# mcu_v06.net
KiCad netlist of a schematic drawn in EAGLE
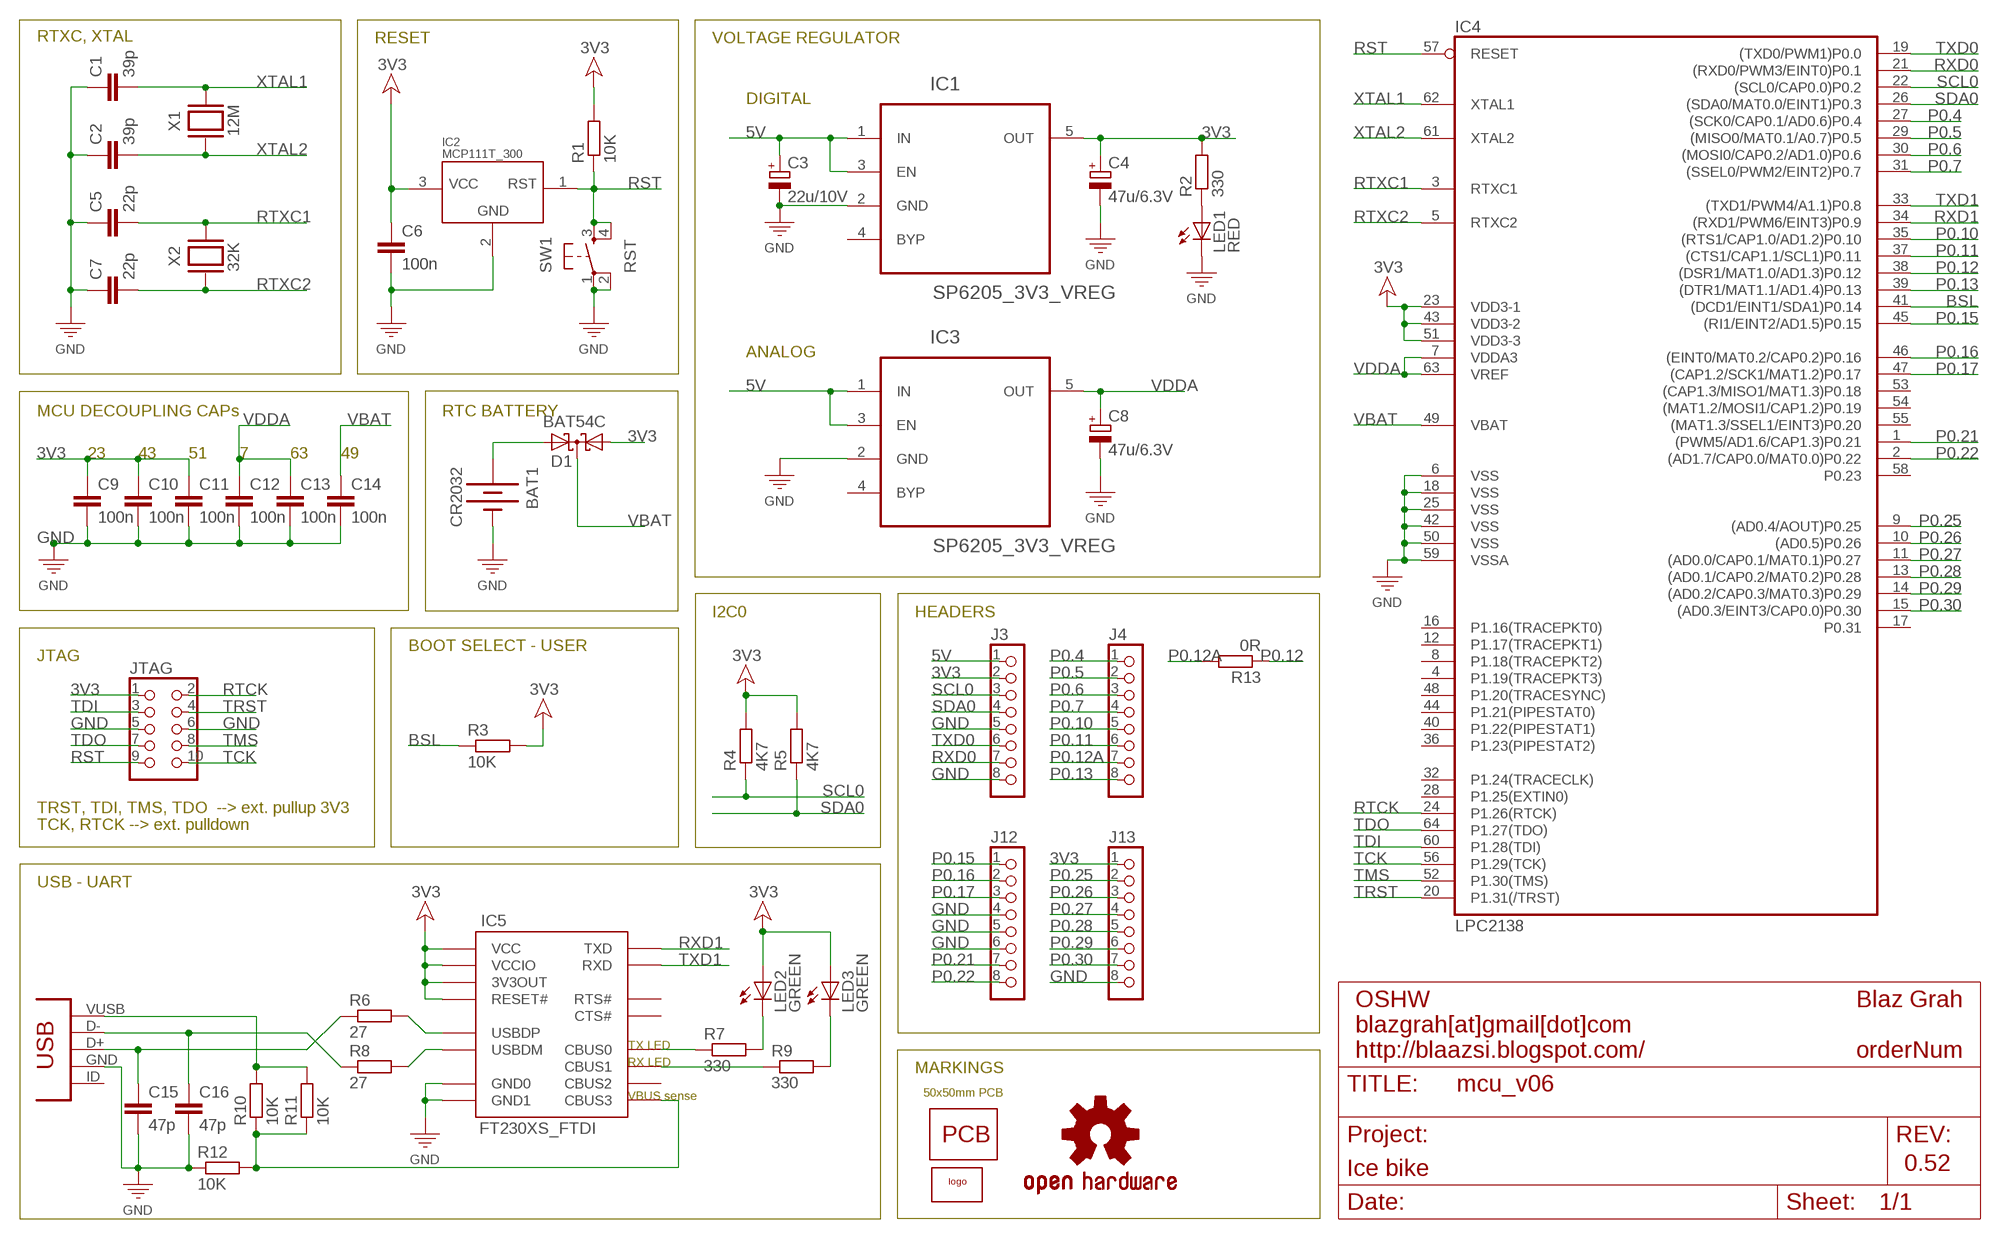
[diagram p0: schematic, sheet 1]

(export (version "E")
  (design (tool "Eeschema 10.0.6"))
  (components
    (comp (ref "BAT1")
      (value "CR2032")
      (footprint "eagle-import:BATTERY_20MM_SMD")
      (libsource (lib "eagle-import") (part "BATTERY20MM"))
    )
    (comp (ref "C1")
      (value "39p")
      (footprint "eagle-import:C0603")
      (libsource (lib "eagle-import") (part "C-EUC0603"))
    )
    (comp (ref "C2")
      (value "39p")
      (footprint "eagle-import:C0603")
      (libsource (lib "eagle-import") (part "C-EUC0603"))
    )
    (comp (ref "C3")
      (value "22u/10V")
      (footprint "eagle-import:SMC_B")
      (libsource (lib "eagle-import") (part "CAPACITOR_POL-SMC_B"))
    )
    (comp (ref "C4")
      (value "47u/6.3V")
      (footprint "eagle-import:SMC_B")
      (libsource (lib "eagle-import") (part "CAPACITOR_POL-SMC_B"))
    )
    (comp (ref "C5")
      (value "22p")
      (footprint "eagle-import:C0603")
      (libsource (lib "eagle-import") (part "C-EUC0603"))
    )
    (comp (ref "C6")
      (value "100n")
      (footprint "eagle-import:C0603")
      (libsource (lib "eagle-import") (part "C-EUC0603"))
    )
    (comp (ref "C7")
      (value "22p")
      (footprint "eagle-import:C0603")
      (libsource (lib "eagle-import") (part "C-EUC0603"))
    )
    (comp (ref "C8")
      (value "47u/6.3V")
      (footprint "eagle-import:SMC_B")
      (libsource (lib "eagle-import") (part "CAPACITOR_POL-SMC_B"))
    )
    (comp (ref "C9")
      (value "100n")
      (footprint "eagle-import:C0603")
      (libsource (lib "eagle-import") (part "C-EUC0603"))
    )
    (comp (ref "C10")
      (value "100n")
      (footprint "eagle-import:C0603")
      (libsource (lib "eagle-import") (part "C-EUC0603"))
    )
    (comp (ref "C11")
      (value "100n")
      (footprint "eagle-import:C0603")
      (libsource (lib "eagle-import") (part "C-EUC0603"))
    )
    (comp (ref "C12")
      (value "100n")
      (footprint "eagle-import:C0603")
      (libsource (lib "eagle-import") (part "C-EUC0603"))
    )
    (comp (ref "C13")
      (value "100n")
      (footprint "eagle-import:C0603")
      (libsource (lib "eagle-import") (part "C-EUC0603"))
    )
    (comp (ref "C14")
      (value "100n")
      (footprint "eagle-import:C0603")
      (libsource (lib "eagle-import") (part "C-EUC0603"))
    )
    (comp (ref "C15")
      (value "47p")
      (footprint "eagle-import:C0603")
      (libsource (lib "eagle-import") (part "C-EUC0603"))
    )
    (comp (ref "C16")
      (value "47p")
      (footprint "eagle-import:C0603")
      (libsource (lib "eagle-import") (part "C-EUC0603"))
    )
    (comp (ref "D1")
      (value "BAT54C")
      (footprint "eagle-import:SOT23")
      (libsource (lib "eagle-import") (part "BAT54C"))
    )
    (comp (ref "DOC")
      (value "FRAME_DINA4_L")
      (footprint "eagle-import:DP_LOGO")
      (fields
        (field (name "AUTHOR") "Blaz Grah")
        (field (name "DATE") "23.4.2012")
        (field (name "LICENSE") "OSHW")
        (field (name "PROJECT") "Ice bike")
        (field (name "REV") "0.52")
        (field (name "URL1") "blazgrah[at]gmail[dot]com")
        (field (name "URL2") "http://blaazsi.blogspot.com/")
      )
      (libsource (lib "eagle-import") (part "FRAME_DINA4_L"))
    )
    (comp (ref "IC1")
      (value "SP6205_3V3_VREG")
      (footprint "eagle-import:SOT23-5")
      (libsource (lib "eagle-import") (part "SP6205_3V3_VREG"))
    )
    (comp (ref "IC2")
      (value "MCP111T_300")
      (footprint "eagle-import:SOT23")
      (libsource (lib "eagle-import") (part "MCP111T_300"))
    )
    (comp (ref "IC3")
      (value "SP6205_3V3_VREG")
      (footprint "eagle-import:SOT23-5")
      (libsource (lib "eagle-import") (part "SP6205_3V3_VREG"))
    )
    (comp (ref "IC4")
      (value "LPC2138")
      (footprint "eagle-import:LQFP64")
      (libsource (lib "eagle-import") (part "LCP2138_LQFP64"))
    )
    (comp (ref "IC5")
      (value "FT230XS_FTDI")
      (footprint "eagle-import:SSOP16")
      (libsource (lib "eagle-import") (part "FT230XS_FTDI"))
    )
    (comp (ref "J3")
      (value "CON_HEADER_1X08-PTH")
      (footprint "eagle-import:M1X8")
      (libsource (lib "eagle-import") (part "CON_HEADER_1X08-PTH"))
    )
    (comp (ref "J4")
      (value "CON_HEADER_1X08-PTH")
      (footprint "eagle-import:M1X8")
      (libsource (lib "eagle-import") (part "CON_HEADER_1X08-PTH"))
    )
    (comp (ref "J12")
      (value "CON_HEADER_1X08-PTH")
      (footprint "eagle-import:M1X8")
      (libsource (lib "eagle-import") (part "CON_HEADER_1X08-PTH"))
    )
    (comp (ref "J13")
      (value "CON_HEADER_1X08-PTH")
      (footprint "eagle-import:M1X8")
      (libsource (lib "eagle-import") (part "CON_HEADER_1X08-PTH"))
    )
    (comp (ref "JTAG")
      (value "CON_HEADER_2X05-PTH+SHROUDED_A")
      (footprint "eagle-import:PINSHRD_PTH_2X05")
      (libsource (lib "eagle-import") (part "CON_HEADER_2X05-PTH+SHROUDED_A"))
    )
    (comp (ref "LED1")
      (value "RED")
      (footprint "eagle-import:LED0805")
      (libsource (lib "eagle-import") (part "LED0805"))
    )
    (comp (ref "LED2")
      (value "GREEN")
      (footprint "eagle-import:LED0805")
      (libsource (lib "eagle-import") (part "LED0805"))
    )
    (comp (ref "LED3")
      (value "GREEN")
      (footprint "eagle-import:LED0805")
      (libsource (lib "eagle-import") (part "LED0805"))
    )
    (comp (ref "LOGO1")
      (value "OSHW-LOGOS")
      (footprint "eagle-import:OSHW-LOGO-S")
      (libsource (lib "eagle-import") (part "OSHW-LOGOS"))
    )
    (comp (ref "PCB1")
      (value "PCB")
      (footprint "eagle-import:PCB_50X50")
      (libsource (lib "eagle-import") (part "PCB"))
    )
    (comp (ref "R1")
      (value "10K")
      (footprint "eagle-import:R0603")
      (libsource (lib "eagle-import") (part "R-EU0603"))
    )
    (comp (ref "R2")
      (value "330")
      (footprint "eagle-import:R0603")
      (libsource (lib "eagle-import") (part "R-EU0603"))
    )
    (comp (ref "R3")
      (value "10K")
      (footprint "eagle-import:R0603")
      (libsource (lib "eagle-import") (part "R-EU0603"))
    )
    (comp (ref "R4")
      (value "4K7")
      (footprint "eagle-import:R0603")
      (libsource (lib "eagle-import") (part "R-EU0603"))
    )
    (comp (ref "R5")
      (value "4K7")
      (footprint "eagle-import:R0603")
      (libsource (lib "eagle-import") (part "R-EU0603"))
    )
    (comp (ref "R6")
      (value "27")
      (footprint "eagle-import:R0603")
      (libsource (lib "eagle-import") (part "R-EU0603"))
    )
    (comp (ref "R7")
      (value "330")
      (footprint "eagle-import:R0603")
      (libsource (lib "eagle-import") (part "R-EU0603"))
    )
    (comp (ref "R8")
      (value "27")
      (footprint "eagle-import:R0603")
      (libsource (lib "eagle-import") (part "R-EU0603"))
    )
    (comp (ref "R9")
      (value "330")
      (footprint "eagle-import:R0603")
      (libsource (lib "eagle-import") (part "R-EU0603"))
    )
    (comp (ref "R10")
      (value "10K")
      (footprint "eagle-import:R0603")
      (libsource (lib "eagle-import") (part "R-EU0603"))
    )
    (comp (ref "R11")
      (value "10K")
      (footprint "eagle-import:R0603")
      (libsource (lib "eagle-import") (part "R-EU0603"))
    )
    (comp (ref "R12")
      (value "10K")
      (footprint "eagle-import:R0603")
      (libsource (lib "eagle-import") (part "R-EU0603"))
    )
    (comp (ref "R13")
      (value "0R")
      (footprint "eagle-import:R0603_JUMP")
      (libsource (lib "eagle-import") (part "R-EU0603J"))
    )
    (comp (ref "SW1")
      (value "RST")
      (footprint "eagle-import:BUTTON_SW_4P_SMD")
      (libsource (lib "eagle-import") (part "TACTIL_BUTTON"))
    )
    (comp (ref "U$13")
      (value "LOGO")
      (footprint "eagle-import:LOGO_SMILE")
      (libsource (lib "eagle-import") (part "LOGO"))
    )
    (comp (ref "USB1")
      (value "CON-USB-F-MINI-B")
      (footprint "eagle-import:CONN_USB_MINI-B")
      (libsource (lib "eagle-import") (part "CON-USB-F-MINI-B"))
    )
    (comp (ref "X1")
      (value "12M")
      (footprint "eagle-import:CRYSTAL_12M_4.8X10.6MM")
      (libsource (lib "eagle-import") (part "CRYSTALSMD_4.8X10.6"))
    )
    (comp (ref "X2")
      (value "32K")
      (footprint "eagle-import:CRYSTAL_32K_SMD")
      (libsource (lib "eagle-import") (part "CRYSTALSMD_32K"))
    )
  )
  (nets
    (net (code "1") (name "/5V") (class "Default")
      (node (ref "C3") (pin "+") (pinfunction "+_+") (pintype "passive"))
      (node (ref "IC1") (pin "1") (pinfunction "IN_1") (pintype "input"))
      (node (ref "IC1") (pin "3") (pinfunction "EN_3") (pintype "input"))
      (node (ref "IC3") (pin "1") (pinfunction "IN_1") (pintype "input"))
      (node (ref "IC3") (pin "3") (pinfunction "EN_3") (pintype "input"))
      (node (ref "J3") (pin "1") (pinfunction "1_1") (pintype "passive"))
    )
    (net (code "2") (name "/BSL") (class "Default")
      (node (ref "IC4") (pin "41") (pinfunction "(DCD1/EINT1/SDA1)P0.14_41") (pintype "bidirectional"))
      (node (ref "R3") (pin "1") (pinfunction "1_1") (pintype "passive"))
    )
    (net (code "3") (name "/P0.4") (class "Default")
      (node (ref "IC4") (pin "27") (pinfunction "(SCK0/CAP0.1/AD0.6)P0.4_27") (pintype "bidirectional"))
      (node (ref "J4") (pin "1") (pinfunction "1_1") (pintype "passive"))
    )
    (net (code "4") (name "/P0.5") (class "Default")
      (node (ref "IC4") (pin "29") (pinfunction "(MISO0/MAT0.1/A0.7)P0.5_29") (pintype "bidirectional"))
      (node (ref "J4") (pin "2") (pinfunction "2_2") (pintype "passive"))
    )
    (net (code "5") (name "/P0.6") (class "Default")
      (node (ref "IC4") (pin "30") (pinfunction "(MOSI0/CAP0.2/AD1.0)P0.6_30") (pintype "bidirectional"))
      (node (ref "J4") (pin "3") (pinfunction "3_3") (pintype "passive"))
    )
    (net (code "6") (name "/P0.7") (class "Default")
      (node (ref "IC4") (pin "31") (pinfunction "(SSEL0/PWM2/EINT2)P0.7_31") (pintype "bidirectional"))
      (node (ref "J4") (pin "4") (pinfunction "4_4") (pintype "passive"))
    )
    (net (code "7") (name "/P0.10") (class "Default")
      (node (ref "IC4") (pin "35") (pinfunction "(RTS1/CAP1.0/AD1.2)P0.10_35") (pintype "bidirectional"))
      (node (ref "J4") (pin "5") (pinfunction "5_5") (pintype "passive"))
    )
    (net (code "8") (name "/P0.11") (class "Default")
      (node (ref "IC4") (pin "37") (pinfunction "(CTS1/CAP1.1/SCL1)P0.11_37") (pintype "bidirectional"))
      (node (ref "J4") (pin "6") (pinfunction "6_6") (pintype "passive"))
    )
    (net (code "9") (name "/P0.12") (class "Default")
      (node (ref "IC4") (pin "38") (pinfunction "(DSR1/MAT1.0/AD1.3)P0.12_38") (pintype "bidirectional"))
      (node (ref "R13") (pin "1") (pinfunction "1_1") (pintype "passive"))
    )
    (net (code "10") (name "/P0.12A") (class "Default")
      (node (ref "J4") (pin "7") (pinfunction "7_7") (pintype "passive"))
      (node (ref "R13") (pin "2") (pinfunction "2_2") (pintype "passive"))
    )
    (net (code "11") (name "/P0.13") (class "Default")
      (node (ref "IC4") (pin "39") (pinfunction "(DTR1/MAT1.1/AD1.4)P0.13_39") (pintype "bidirectional"))
      (node (ref "J4") (pin "8") (pinfunction "8_8") (pintype "passive"))
    )
    (net (code "12") (name "/P0.15") (class "Default")
      (node (ref "IC4") (pin "45") (pinfunction "(RI1/EINT2/AD1.5)P0.15_45") (pintype "bidirectional"))
      (node (ref "J12") (pin "1") (pinfunction "1_1") (pintype "passive"))
    )
    (net (code "13") (name "/P0.16") (class "Default")
      (node (ref "IC4") (pin "46") (pinfunction "(EINT0/MAT0.2/CAP0.2)P0.16_46") (pintype "bidirectional"))
      (node (ref "J12") (pin "2") (pinfunction "2_2") (pintype "passive"))
    )
    (net (code "14") (name "/P0.17") (class "Default")
      (node (ref "IC4") (pin "47") (pinfunction "(CAP1.2/SCK1/MAT1.2)P0.17_47") (pintype "bidirectional"))
      (node (ref "J12") (pin "3") (pinfunction "3_3") (pintype "passive"))
    )
    (net (code "15") (name "/P0.21") (class "Default")
      (node (ref "IC4") (pin "1") (pinfunction "(PWM5/AD1.6/CAP1.3)P0.21_1") (pintype "bidirectional"))
      (node (ref "J12") (pin "7") (pinfunction "7_7") (pintype "passive"))
    )
    (net (code "16") (name "/P0.22") (class "Default")
      (node (ref "IC4") (pin "2") (pinfunction "(AD1.7/CAP0.0/MAT0.0)P0.22_2") (pintype "bidirectional"))
      (node (ref "J12") (pin "8") (pinfunction "8_8") (pintype "passive"))
    )
    (net (code "17") (name "/P0.25") (class "Default")
      (node (ref "IC4") (pin "9") (pinfunction "(AD0.4/AOUT)P0.25_9") (pintype "bidirectional"))
      (node (ref "J13") (pin "2") (pinfunction "2_2") (pintype "passive"))
    )
    (net (code "18") (name "/P0.26") (class "Default")
      (node (ref "IC4") (pin "10") (pinfunction "(AD0.5)P0.26_10") (pintype "bidirectional"))
      (node (ref "J13") (pin "3") (pinfunction "3_3") (pintype "passive"))
    )
    (net (code "19") (name "/P0.27") (class "Default")
      (node (ref "IC4") (pin "11") (pinfunction "(AD0.0/CAP0.1/MAT0.1)P0.27_11") (pintype "bidirectional"))
      (node (ref "J13") (pin "4") (pinfunction "4_4") (pintype "passive"))
    )
    (net (code "20") (name "/P0.28") (class "Default")
      (node (ref "IC4") (pin "13") (pinfunction "(AD0.1/CAP0.2/MAT0.2)P0.28_13") (pintype "bidirectional"))
      (node (ref "J13") (pin "5") (pinfunction "5_5") (pintype "passive"))
    )
    (net (code "21") (name "/P0.29") (class "Default")
      (node (ref "IC4") (pin "14") (pinfunction "(AD0.2/CAP0.3/MAT0.3)P0.29_14") (pintype "bidirectional"))
      (node (ref "J13") (pin "6") (pinfunction "6_6") (pintype "passive"))
    )
    (net (code "22") (name "/P0.30") (class "Default")
      (node (ref "IC4") (pin "15") (pinfunction "(AD0.3/EINT3/CAP0.0)P0.30_15") (pintype "bidirectional"))
      (node (ref "J13") (pin "7") (pinfunction "7_7") (pintype "passive"))
    )
    (net (code "23") (name "/RST") (class "Default")
      (node (ref "IC2") (pin "1") (pinfunction "RST_1") (pintype "output"))
      (node (ref "IC4") (pin "57") (pinfunction "RESET_57") (pintype "input"))
      (node (ref "JTAG") (pin "9") (pinfunction "9_9") (pintype "passive"))
      (node (ref "R1") (pin "1") (pinfunction "1_1") (pintype "passive"))
      (node (ref "SW1") (pin "3") (pinfunction "3_3") (pintype "passive"))
      (node (ref "SW1") (pin "4") (pinfunction "4_4") (pintype "passive"))
    )
    (net (code "24") (name "/RTCK") (class "Default")
      (node (ref "IC4") (pin "24") (pinfunction "P1.26(RTCK)_24") (pintype "bidirectional"))
      (node (ref "JTAG") (pin "2") (pinfunction "2_2") (pintype "passive"))
    )
    (net (code "25") (name "/RTXC1") (class "Default")
      (node (ref "C5") (pin "2") (pinfunction "2_2") (pintype "passive"))
      (node (ref "IC4") (pin "3") (pinfunction "RTXC1_3") (pintype "input"))
      (node (ref "X2") (pin "X2") (pinfunction "2_X2") (pintype "passive"))
    )
    (net (code "26") (name "/RTXC2") (class "Default")
      (node (ref "C7") (pin "2") (pinfunction "2_2") (pintype "passive"))
      (node (ref "IC4") (pin "5") (pinfunction "RTXC2_5") (pintype "output"))
      (node (ref "X2") (pin "X1") (pinfunction "1_X1") (pintype "passive"))
    )
    (net (code "27") (name "/RXD0") (class "Default")
      (node (ref "IC4") (pin "21") (pinfunction "(RXD0/PWM3/EINT0)P0.1_21") (pintype "bidirectional"))
      (node (ref "J3") (pin "7") (pinfunction "7_7") (pintype "passive"))
    )
    (net (code "28") (name "/RXD1") (class "Default")
      (node (ref "IC4") (pin "34") (pinfunction "(RXD1/PWM6/EINT3)P0.9_34") (pintype "bidirectional"))
      (node (ref "IC5") (pin "P$1") (pinfunction "TXD_P$1") (pintype "bidirectional"))
    )
    (net (code "29") (name "/SCL0") (class "Default")
      (node (ref "IC4") (pin "22") (pinfunction "(SCL0/CAP0.0)P0.2_22") (pintype "bidirectional"))
      (node (ref "J3") (pin "3") (pinfunction "3_3") (pintype "passive"))
      (node (ref "R4") (pin "1") (pinfunction "1_1") (pintype "passive"))
    )
    (net (code "30") (name "/SDA0") (class "Default")
      (node (ref "IC4") (pin "26") (pinfunction "(SDA0/MAT0.0/EINT1)P0.3_26") (pintype "bidirectional"))
      (node (ref "J3") (pin "4") (pinfunction "4_4") (pintype "passive"))
      (node (ref "R5") (pin "1") (pinfunction "1_1") (pintype "passive"))
    )
    (net (code "31") (name "/TCK") (class "Default")
      (node (ref "IC4") (pin "56") (pinfunction "P1.29(TCK)_56") (pintype "bidirectional"))
      (node (ref "JTAG") (pin "10") (pinfunction "10_10") (pintype "passive"))
    )
    (net (code "32") (name "/TDI") (class "Default")
      (node (ref "IC4") (pin "60") (pinfunction "P1.28(TDI)_60") (pintype "bidirectional"))
      (node (ref "JTAG") (pin "3") (pinfunction "3_3") (pintype "passive"))
    )
    (net (code "33") (name "/TDO") (class "Default")
      (node (ref "IC4") (pin "64") (pinfunction "P1.27(TDO)_64") (pintype "bidirectional"))
      (node (ref "JTAG") (pin "7") (pinfunction "7_7") (pintype "passive"))
    )
    (net (code "34") (name "/TMS") (class "Default")
      (node (ref "IC4") (pin "52") (pinfunction "P1.30(TMS)_52") (pintype "bidirectional"))
      (node (ref "JTAG") (pin "8") (pinfunction "8_8") (pintype "passive"))
    )
    (net (code "35") (name "/TRST") (class "Default")
      (node (ref "IC4") (pin "20") (pinfunction "P1.31(/TRST)_20") (pintype "bidirectional"))
      (node (ref "JTAG") (pin "4") (pinfunction "4_4") (pintype "passive"))
    )
    (net (code "36") (name "/TXD0") (class "Default")
      (node (ref "IC4") (pin "19") (pinfunction "(TXD0/PWM1)P0.0_19") (pintype "bidirectional"))
      (node (ref "J3") (pin "6") (pinfunction "6_6") (pintype "passive"))
    )
    (net (code "37") (name "/TXD1") (class "Default")
      (node (ref "IC4") (pin "33") (pinfunction "(TXD1/PWM4/A1.1)P0.8_33") (pintype "bidirectional"))
      (node (ref "IC5") (pin "P$4") (pinfunction "RXD_P$4") (pintype "bidirectional"))
    )
    (net (code "38") (name "/VBAT") (class "Default")
      (node (ref "C14") (pin "1") (pinfunction "1_1") (pintype "passive"))
      (node (ref "D1") (pin "3") (pinfunction "CC_3") (pintype "passive"))
      (node (ref "IC4") (pin "49") (pinfunction "VBAT_49") (pintype "power_in"))
    )
    (net (code "39") (name "/VDDA") (class "Default")
      (node (ref "C12") (pin "1") (pinfunction "1_1") (pintype "passive"))
      (node (ref "C13") (pin "1") (pinfunction "1_1") (pintype "passive"))
      (node (ref "C8") (pin "+") (pinfunction "+_+") (pintype "passive"))
      (node (ref "IC3") (pin "5") (pinfunction "OUT_5") (pintype "power_in"))
      (node (ref "IC4") (pin "63") (pinfunction "VREF_63") (pintype "input"))
      (node (ref "IC4") (pin "7") (pinfunction "VDDA3_7") (pintype "power_in"))
    )
    (net (code "40") (name "/XTAL1") (class "Default")
      (node (ref "C1") (pin "2") (pinfunction "2_2") (pintype "passive"))
      (node (ref "IC4") (pin "62") (pinfunction "XTAL1_62") (pintype "input"))
      (node (ref "X1") (pin "P$2") (pinfunction "2_P$2") (pintype "passive"))
    )
    (net (code "41") (name "/XTAL2") (class "Default")
      (node (ref "C2") (pin "2") (pinfunction "2_2") (pintype "passive"))
      (node (ref "IC4") (pin "61") (pinfunction "XTAL2_61") (pintype "output"))
      (node (ref "X1") (pin "P$1") (pinfunction "1_P$1") (pintype "passive"))
    )
    (net (code "42") (name "3V3") (class "Default")
      (node (ref "C10") (pin "1") (pinfunction "1_1") (pintype "passive"))
      (node (ref "C11") (pin "1") (pinfunction "1_1") (pintype "passive"))
      (node (ref "C4") (pin "+") (pinfunction "+_+") (pintype "passive"))
      (node (ref "C6") (pin "1") (pinfunction "1_1") (pintype "passive"))
      (node (ref "C9") (pin "1") (pinfunction "1_1") (pintype "passive"))
      (node (ref "D1") (pin "1") (pinfunction "A1_1") (pintype "passive"))
      (node (ref "IC1") (pin "5") (pinfunction "OUT_5") (pintype "power_in"))
      (node (ref "IC2") (pin "3") (pinfunction "VCC_3") (pintype "input"))
      (node (ref "IC4") (pin "23") (pinfunction "VDD3-1_23") (pintype "power_in"))
      (node (ref "IC4") (pin "43") (pinfunction "VDD3-2_43") (pintype "power_in"))
      (node (ref "IC4") (pin "51") (pinfunction "VDD3-3_51") (pintype "power_in"))
      (node (ref "IC5") (pin "P$10") (pinfunction "3V3OUT_P$10") (pintype "power_in"))
      (node (ref "IC5") (pin "P$11") (pinfunction "RESET#_P$11") (pintype "bidirectional"))
      (node (ref "IC5") (pin "P$12") (pinfunction "VCC_P$12") (pintype "power_in"))
      (node (ref "IC5") (pin "P$3") (pinfunction "VCCIO_P$3") (pintype "power_in"))
      (node (ref "J13") (pin "1") (pinfunction "1_1") (pintype "passive"))
      (node (ref "J3") (pin "2") (pinfunction "2_2") (pintype "passive"))
      (node (ref "JTAG") (pin "1") (pinfunction "1_1") (pintype "passive"))
      (node (ref "LED2") (pin "A") (pinfunction "A_A") (pintype "passive"))
      (node (ref "LED3") (pin "A") (pinfunction "A_A") (pintype "passive"))
      (node (ref "R1") (pin "2") (pinfunction "2_2") (pintype "passive"))
      (node (ref "R2") (pin "2") (pinfunction "2_2") (pintype "passive"))
      (node (ref "R3") (pin "2") (pinfunction "2_2") (pintype "passive"))
      (node (ref "R4") (pin "2") (pinfunction "2_2") (pintype "passive"))
      (node (ref "R5") (pin "2") (pinfunction "2_2") (pintype "passive"))
    )
    (net (code "43") (name "GND") (class "Default")
      (node (ref "BAT1") (pin "NEG") (pinfunction "NEG_NEG") (pintype "power_in"))
      (node (ref "C1") (pin "1") (pinfunction "1_1") (pintype "passive"))
      (node (ref "C10") (pin "2") (pinfunction "2_2") (pintype "passive"))
      (node (ref "C11") (pin "2") (pinfunction "2_2") (pintype "passive"))
      (node (ref "C12") (pin "2") (pinfunction "2_2") (pintype "passive"))
      (node (ref "C13") (pin "2") (pinfunction "2_2") (pintype "passive"))
      (node (ref "C14") (pin "2") (pinfunction "2_2") (pintype "passive"))
      (node (ref "C15") (pin "2") (pinfunction "2_2") (pintype "passive"))
      (node (ref "C16") (pin "2") (pinfunction "2_2") (pintype "passive"))
      (node (ref "C2") (pin "1") (pinfunction "1_1") (pintype "passive"))
      (node (ref "C3") (pin "-") (pinfunction "-_-") (pintype "passive"))
      (node (ref "C4") (pin "-") (pinfunction "-_-") (pintype "passive"))
      (node (ref "C5") (pin "1") (pinfunction "1_1") (pintype "passive"))
      (node (ref "C6") (pin "2") (pinfunction "2_2") (pintype "passive"))
      (node (ref "C7") (pin "1") (pinfunction "1_1") (pintype "passive"))
      (node (ref "C8") (pin "-") (pinfunction "-_-") (pintype "passive"))
      (node (ref "C9") (pin "2") (pinfunction "2_2") (pintype "passive"))
      (node (ref "IC1") (pin "2") (pinfunction "GND_2") (pintype "power_in"))
      (node (ref "IC2") (pin "2") (pinfunction "GND_2") (pintype "power_in"))
      (node (ref "IC3") (pin "2") (pinfunction "GND_2") (pintype "power_in"))
      (node (ref "IC4") (pin "18") (pinfunction "VSS_18") (pintype "power_in"))
      (node (ref "IC4") (pin "25") (pinfunction "VSS_25") (pintype "power_in"))
      (node (ref "IC4") (pin "42") (pinfunction "VSS_42") (pintype "power_in"))
      (node (ref "IC4") (pin "50") (pinfunction "VSS_50") (pintype "power_in"))
      (node (ref "IC4") (pin "59") (pinfunction "VSSA_59") (pintype "power_in"))
      (node (ref "IC4") (pin "6") (pinfunction "VSS_6") (pintype "power_in"))
      (node (ref "IC5") (pin "P$13") (pinfunction "GND1_P$13") (pintype "power_in"))
      (node (ref "IC5") (pin "P$5") (pinfunction "GND0_P$5") (pintype "power_in"))
      (node (ref "J12") (pin "4") (pinfunction "4_4") (pintype "passive"))
      (node (ref "J12") (pin "5") (pinfunction "5_5") (pintype "passive"))
      (node (ref "J12") (pin "6") (pinfunction "6_6") (pintype "passive"))
      (node (ref "J13") (pin "8") (pinfunction "8_8") (pintype "passive"))
      (node (ref "J3") (pin "5") (pinfunction "5_5") (pintype "passive"))
      (node (ref "J3") (pin "8") (pinfunction "8_8") (pintype "passive"))
      (node (ref "JTAG") (pin "5") (pinfunction "5_5") (pintype "passive"))
      (node (ref "JTAG") (pin "6") (pinfunction "6_6") (pintype "passive"))
      (node (ref "LED1") (pin "C") (pinfunction "C_C") (pintype "passive"))
      (node (ref "R12") (pin "1") (pinfunction "1_1") (pintype "passive"))
      (node (ref "SW1") (pin "1") (pinfunction "1_1") (pintype "passive"))
      (node (ref "SW1") (pin "2") (pinfunction "2_2") (pintype "passive"))
      (node (ref "USB1") (pin "GND") (pinfunction "GND_GND") (pintype "bidirectional"))
    )
    (net (code "44") (name "Net-(C15-Pad1)") (class "Default")
      (node (ref "C15") (pin "1") (pinfunction "1_1") (pintype "passive"))
      (node (ref "R6") (pin "1") (pinfunction "1_1") (pintype "passive"))
      (node (ref "USB1") (pin "D+") (pinfunction "D+_D+") (pintype "bidirectional"))
    )
    (net (code "45") (name "Net-(C16-Pad1)") (class "Default")
      (node (ref "C16") (pin "1") (pinfunction "1_1") (pintype "passive"))
      (node (ref "R8") (pin "1") (pinfunction "1_1") (pintype "passive"))
      (node (ref "USB1") (pin "D-") (pinfunction "D-_D-") (pintype "bidirectional"))
    )
    (net (code "46") (name "Net-(D1-A2)") (class "Default")
      (node (ref "BAT1") (pin "POS1") (pinfunction "POZ_POS1") (pintype "power_in"))
      (node (ref "BAT1") (pin "POS2") (pinfunction "POZ_POS2") (pintype "power_in"))
      (node (ref "D1") (pin "2") (pinfunction "A2_2") (pintype "passive"))
    )
    (net (code "47") (name "Net-(IC5-CBUS0)") (class "Default")
      (node (ref "IC5") (pin "P$15") (pinfunction "CBUS0_P$15") (pintype "bidirectional"))
      (node (ref "R7") (pin "1") (pinfunction "1_1") (pintype "passive"))
    )
    (net (code "48") (name "Net-(IC5-CBUS1)") (class "Default")
      (node (ref "IC5") (pin "P$14") (pinfunction "CBUS1_P$14") (pintype "bidirectional"))
      (node (ref "R9") (pin "1") (pinfunction "1_1") (pintype "passive"))
    )
    (net (code "49") (name "Net-(IC5-CBUS3)") (class "Default")
      (node (ref "IC5") (pin "P$16") (pinfunction "CBUS3_P$16") (pintype "bidirectional"))
      (node (ref "R10") (pin "1") (pinfunction "1_1") (pintype "passive"))
      (node (ref "R11") (pin "1") (pinfunction "1_1") (pintype "passive"))
      (node (ref "R12") (pin "2") (pinfunction "2_2") (pintype "passive"))
    )
    (net (code "50") (name "Net-(IC5-USBDM)") (class "Default")
      (node (ref "IC5") (pin "P$9") (pinfunction "USBDM_P$9") (pintype "bidirectional"))
      (node (ref "R8") (pin "2") (pinfunction "2_2") (pintype "passive"))
    )
    (net (code "51") (name "Net-(IC5-USBDP)") (class "Default")
      (node (ref "IC5") (pin "P$8") (pinfunction "USBDP_P$8") (pintype "bidirectional"))
      (node (ref "R6") (pin "2") (pinfunction "2_2") (pintype "passive"))
    )
    (net (code "52") (name "Net-(LED1-PadA)") (class "Default")
      (node (ref "LED1") (pin "A") (pinfunction "A_A") (pintype "passive"))
      (node (ref "R2") (pin "1") (pinfunction "1_1") (pintype "passive"))
    )
    (net (code "53") (name "Net-(LED2-PadC)") (class "Default")
      (node (ref "LED2") (pin "C") (pinfunction "C_C") (pintype "passive"))
      (node (ref "R7") (pin "2") (pinfunction "2_2") (pintype "passive"))
    )
    (net (code "54") (name "Net-(LED3-PadC)") (class "Default")
      (node (ref "LED3") (pin "C") (pinfunction "C_C") (pintype "passive"))
      (node (ref "R9") (pin "2") (pinfunction "2_2") (pintype "passive"))
    )
    (net (code "55") (name "Net-(R10-Pad2)") (class "Default")
      (node (ref "R10") (pin "2") (pinfunction "2_2") (pintype "passive"))
      (node (ref "R11") (pin "2") (pinfunction "2_2") (pintype "passive"))
      (node (ref "USB1") (pin "VUSB") (pinfunction "VUSB_VUSB") (pintype "bidirectional"))
    )
    (net (code "56") (name "unconnected-(IC1-BYP-Pad4)") (class "Default")
      (node (ref "IC1") (pin "4") (pinfunction "BYP_4") (pintype "no_connect"))
    )
    (net (code "57") (name "unconnected-(IC3-BYP-Pad4)") (class "Default")
      (node (ref "IC3") (pin "4") (pinfunction "BYP_4") (pintype "no_connect"))
    )
    (net (code "58") (name "unconnected-(IC4-(CAP1.3{slash}MISO1{slash}MAT1.3)P0.18-Pad53)") (class "Default")
      (node (ref "IC4") (pin "53") (pinfunction "(CAP1.3/MISO1/MAT1.3)P0.18_53") (pintype "bidirectional"))
    )
    (net (code "59") (name "unconnected-(IC4-(MAT1.2{slash}MOSI1{slash}CAP1.2)P0.19-Pad54)") (class "Default")
      (node (ref "IC4") (pin "54") (pinfunction "(MAT1.2/MOSI1/CAP1.2)P0.19_54") (pintype "bidirectional"))
    )
    (net (code "60") (name "unconnected-(IC4-(MAT1.3{slash}SSEL1{slash}EINT3)P0.20-Pad55)") (class "Default")
      (node (ref "IC4") (pin "55") (pinfunction "(MAT1.3/SSEL1/EINT3)P0.20_55") (pintype "bidirectional"))
    )
    (net (code "61") (name "unconnected-(IC4-P0.23-Pad58)") (class "Default")
      (node (ref "IC4") (pin "58") (pinfunction "P0.23_58") (pintype "bidirectional"))
    )
    (net (code "62") (name "unconnected-(IC4-P0.31-Pad17)") (class "Default")
      (node (ref "IC4") (pin "17") (pinfunction "P0.31_17") (pintype "output"))
    )
    (net (code "63") (name "unconnected-(IC4-P1.16(TRACEPKT0)-Pad16)") (class "Default")
      (node (ref "IC4") (pin "16") (pinfunction "P1.16(TRACEPKT0)_16") (pintype "bidirectional"))
    )
    (net (code "64") (name "unconnected-(IC4-P1.17(TRACEPKT1)-Pad12)") (class "Default")
      (node (ref "IC4") (pin "12") (pinfunction "P1.17(TRACEPKT1)_12") (pintype "bidirectional"))
    )
    (net (code "65") (name "unconnected-(IC4-P1.18(TRACEPKT2)-Pad8)") (class "Default")
      (node (ref "IC4") (pin "8") (pinfunction "P1.18(TRACEPKT2)_8") (pintype "bidirectional"))
    )
    (net (code "66") (name "unconnected-(IC4-P1.19(TRACEPKT3)-Pad4)") (class "Default")
      (node (ref "IC4") (pin "4") (pinfunction "P1.19(TRACEPKT3)_4") (pintype "bidirectional"))
    )
    (net (code "67") (name "unconnected-(IC4-P1.20(TRACESYNC)-Pad48)") (class "Default")
      (node (ref "IC4") (pin "48") (pinfunction "P1.20(TRACESYNC)_48") (pintype "bidirectional"))
    )
    (net (code "68") (name "unconnected-(IC4-P1.21(PIPESTAT0)-Pad44)") (class "Default")
      (node (ref "IC4") (pin "44") (pinfunction "P1.21(PIPESTAT0)_44") (pintype "bidirectional"))
    )
    (net (code "69") (name "unconnected-(IC4-P1.22(PIPESTAT1)-Pad40)") (class "Default")
      (node (ref "IC4") (pin "40") (pinfunction "P1.22(PIPESTAT1)_40") (pintype "bidirectional"))
    )
    (net (code "70") (name "unconnected-(IC4-P1.23(PIPESTAT2)-Pad36)") (class "Default")
      (node (ref "IC4") (pin "36") (pinfunction "P1.23(PIPESTAT2)_36") (pintype "bidirectional"))
    )
    (net (code "71") (name "unconnected-(IC4-P1.24(TRACECLK)-Pad32)") (class "Default")
      (node (ref "IC4") (pin "32") (pinfunction "P1.24(TRACECLK)_32") (pintype "bidirectional"))
    )
    (net (code "72") (name "unconnected-(IC4-P1.25(EXTIN0)-Pad28)") (class "Default")
      (node (ref "IC4") (pin "28") (pinfunction "P1.25(EXTIN0)_28") (pintype "bidirectional"))
    )
    (net (code "73") (name "unconnected-(IC5-CBUS2-PadP$7)") (class "Default")
      (node (ref "IC5") (pin "P$7") (pinfunction "CBUS2_P$7") (pintype "bidirectional"))
    )
    (net (code "74") (name "unconnected-(IC5-CTS#-PadP$6)") (class "Default")
      (node (ref "IC5") (pin "P$6") (pinfunction "CTS#_P$6") (pintype "bidirectional"))
    )
    (net (code "75") (name "unconnected-(IC5-RTS#-PadP$2)") (class "Default")
      (node (ref "IC5") (pin "P$2") (pinfunction "RTS#_P$2") (pintype "bidirectional"))
    )
    (net (code "76") (name "unconnected-(USB1B-USBID-PadID)") (class "Default")
      (node (ref "USB1") (pin "ID") (pinfunction "USBID_ID") (pintype "bidirectional"))
    )
  )
)
